# uc_sram.net
KiCad netlist of a schematic drawn in Altium Designer
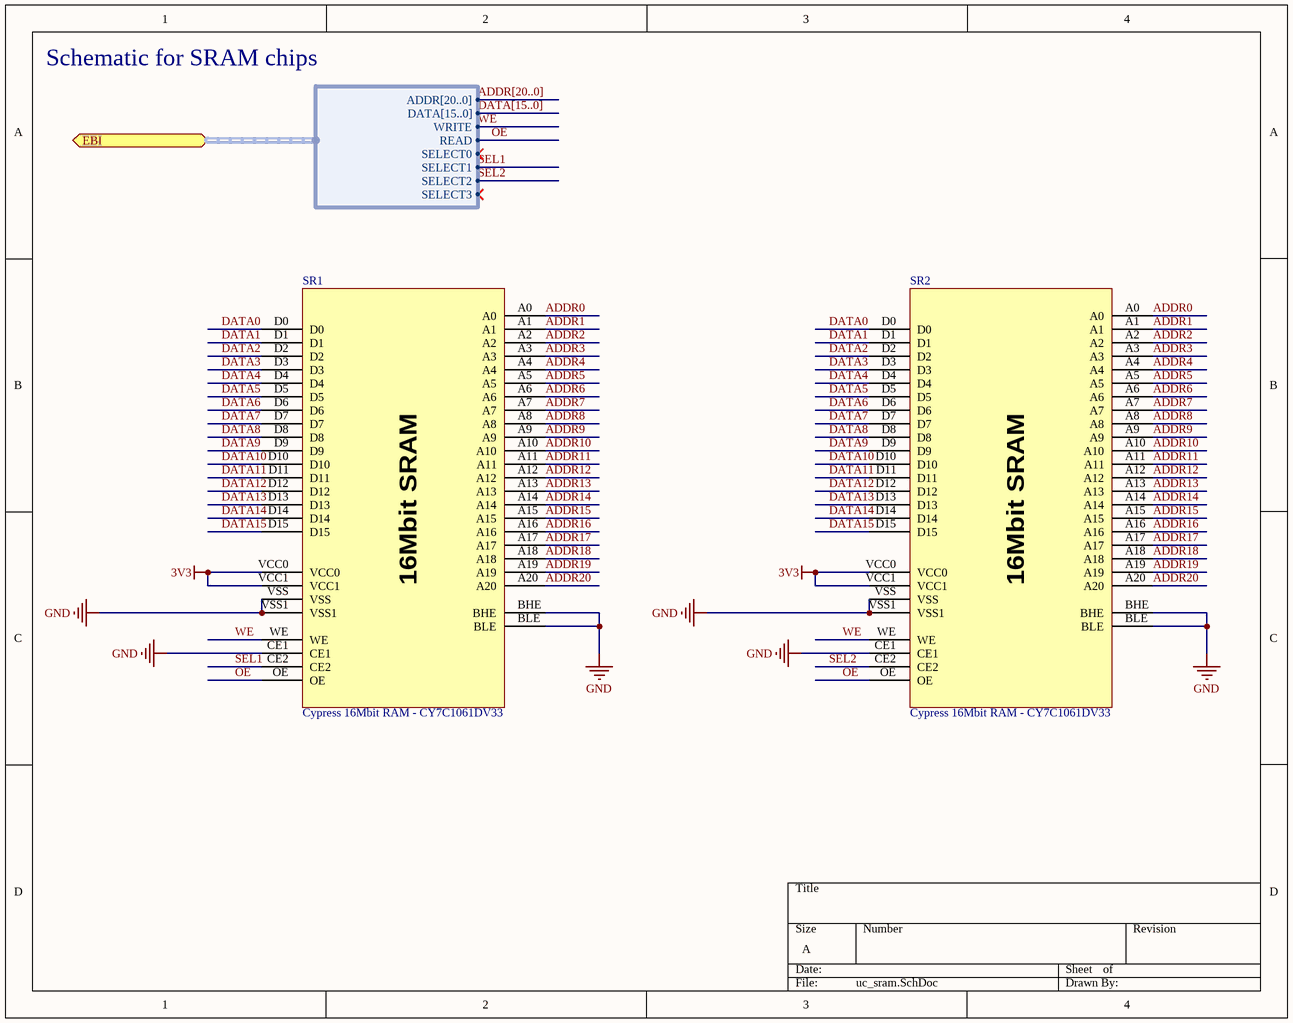
[diagram p0: uc_sram.SchDoc]

(export (version "E")
  (design (tool "Eeschema 10.0.6"))
  (components
    (comp (ref "SR1")
      (value "Cypress 16Mbit RAM - CY7C1061DV33")
      (footprint "BGA48C75P8X6_950X800X100")
      (libsource (lib "ORLY_Lib") (part "Cypress 16Mbit RAM - CY7C1061DV33"))
    )
    (comp (ref "SR2")
      (value "Cypress 16Mbit RAM - CY7C1061DV33")
      (footprint "BGA48C75P8X6_950X800X100")
      (libsource (lib "ORLY_Lib") (part "Cypress 16Mbit RAM - CY7C1061DV33"))
    )
  )
  (nets
    (net (code "2") (name "/ADDR0") (class "Default")
      (node (ref "SR1") (pin "A0") (pinfunction "A0_A0") (pintype "passive"))
      (node (ref "SR2") (pin "A0") (pinfunction "A0_A0") (pintype "passive"))
    )
    (net (code "3") (name "/ADDR1") (class "Default")
      (node (ref "SR1") (pin "A1") (pinfunction "A1_A1") (pintype "passive"))
      (node (ref "SR2") (pin "A1") (pinfunction "A1_A1") (pintype "passive"))
    )
    (net (code "4") (name "/ADDR2") (class "Default")
      (node (ref "SR1") (pin "A2") (pinfunction "A2_A2") (pintype "passive"))
      (node (ref "SR2") (pin "A2") (pinfunction "A2_A2") (pintype "passive"))
    )
    (net (code "5") (name "/ADDR3") (class "Default")
      (node (ref "SR1") (pin "A3") (pinfunction "A3_A3") (pintype "passive"))
      (node (ref "SR2") (pin "A3") (pinfunction "A3_A3") (pintype "passive"))
    )
    (net (code "6") (name "/ADDR4") (class "Default")
      (node (ref "SR1") (pin "A4") (pinfunction "A4_A4") (pintype "passive"))
      (node (ref "SR2") (pin "A4") (pinfunction "A4_A4") (pintype "passive"))
    )
    (net (code "7") (name "/ADDR5") (class "Default")
      (node (ref "SR1") (pin "A5") (pinfunction "A5_A5") (pintype "passive"))
      (node (ref "SR2") (pin "A5") (pinfunction "A5_A5") (pintype "passive"))
    )
    (net (code "8") (name "/ADDR6") (class "Default")
      (node (ref "SR1") (pin "A6") (pinfunction "A6_A6") (pintype "passive"))
      (node (ref "SR2") (pin "A6") (pinfunction "A6_A6") (pintype "passive"))
    )
    (net (code "9") (name "/ADDR7") (class "Default")
      (node (ref "SR1") (pin "A7") (pinfunction "A7_A7") (pintype "passive"))
      (node (ref "SR2") (pin "A7") (pinfunction "A7_A7") (pintype "passive"))
    )
    (net (code "10") (name "/ADDR8") (class "Default")
      (node (ref "SR1") (pin "A8") (pinfunction "A8_A8") (pintype "passive"))
      (node (ref "SR2") (pin "A8") (pinfunction "A8_A8") (pintype "passive"))
    )
    (net (code "11") (name "/ADDR9") (class "Default")
      (node (ref "SR1") (pin "A9") (pinfunction "A9_A9") (pintype "passive"))
      (node (ref "SR2") (pin "A9") (pinfunction "A9_A9") (pintype "passive"))
    )
    (net (code "12") (name "/ADDR10") (class "Default")
      (node (ref "SR1") (pin "A10") (pinfunction "A10_A10") (pintype "passive"))
      (node (ref "SR2") (pin "A10") (pinfunction "A10_A10") (pintype "passive"))
    )
    (net (code "13") (name "/ADDR11") (class "Default")
      (node (ref "SR1") (pin "A11") (pinfunction "A11_A11") (pintype "passive"))
      (node (ref "SR2") (pin "A11") (pinfunction "A11_A11") (pintype "passive"))
    )
    (net (code "14") (name "/ADDR12") (class "Default")
      (node (ref "SR1") (pin "A12") (pinfunction "A12_A12") (pintype "passive"))
      (node (ref "SR2") (pin "A12") (pinfunction "A12_A12") (pintype "passive"))
    )
    (net (code "15") (name "/ADDR13") (class "Default")
      (node (ref "SR1") (pin "A13") (pinfunction "A13_A13") (pintype "passive"))
      (node (ref "SR2") (pin "A13") (pinfunction "A13_A13") (pintype "passive"))
    )
    (net (code "16") (name "/ADDR14") (class "Default")
      (node (ref "SR1") (pin "A14") (pinfunction "A14_A14") (pintype "passive"))
      (node (ref "SR2") (pin "A14") (pinfunction "A14_A14") (pintype "passive"))
    )
    (net (code "17") (name "/ADDR15") (class "Default")
      (node (ref "SR1") (pin "A15") (pinfunction "A15_A15") (pintype "passive"))
      (node (ref "SR2") (pin "A15") (pinfunction "A15_A15") (pintype "passive"))
    )
    (net (code "18") (name "/ADDR16") (class "Default")
      (node (ref "SR1") (pin "A16") (pinfunction "A16_A16") (pintype "passive"))
      (node (ref "SR2") (pin "A16") (pinfunction "A16_A16") (pintype "passive"))
    )
    (net (code "19") (name "/ADDR17") (class "Default")
      (node (ref "SR1") (pin "A17") (pinfunction "A17_A17") (pintype "passive"))
      (node (ref "SR2") (pin "A17") (pinfunction "A17_A17") (pintype "passive"))
    )
    (net (code "20") (name "/ADDR18") (class "Default")
      (node (ref "SR1") (pin "A18") (pinfunction "A18_A18") (pintype "passive"))
      (node (ref "SR2") (pin "A18") (pinfunction "A18_A18") (pintype "passive"))
    )
    (net (code "21") (name "/ADDR19") (class "Default")
      (node (ref "SR1") (pin "A19") (pinfunction "A19_A19") (pintype "passive"))
      (node (ref "SR2") (pin "A19") (pinfunction "A19_A19") (pintype "passive"))
    )
    (net (code "22") (name "/ADDR20") (class "Default")
      (node (ref "SR1") (pin "A20") (pinfunction "A20_A20") (pintype "passive"))
      (node (ref "SR2") (pin "A20") (pinfunction "A20_A20") (pintype "passive"))
    )
    (net (code "24") (name "/DATA0") (class "Default")
      (node (ref "SR1") (pin "D0") (pinfunction "D0_D0") (pintype "passive"))
      (node (ref "SR2") (pin "D0") (pinfunction "D0_D0") (pintype "passive"))
    )
    (net (code "25") (name "/DATA1") (class "Default")
      (node (ref "SR1") (pin "D1") (pinfunction "D1_D1") (pintype "passive"))
      (node (ref "SR2") (pin "D1") (pinfunction "D1_D1") (pintype "passive"))
    )
    (net (code "26") (name "/DATA2") (class "Default")
      (node (ref "SR1") (pin "D2") (pinfunction "D2_D2") (pintype "passive"))
      (node (ref "SR2") (pin "D2") (pinfunction "D2_D2") (pintype "passive"))
    )
    (net (code "27") (name "/DATA3") (class "Default")
      (node (ref "SR1") (pin "D3") (pinfunction "D3_D3") (pintype "passive"))
      (node (ref "SR2") (pin "D3") (pinfunction "D3_D3") (pintype "passive"))
    )
    (net (code "28") (name "/DATA4") (class "Default")
      (node (ref "SR1") (pin "D4") (pinfunction "D4_D4") (pintype "passive"))
      (node (ref "SR2") (pin "D4") (pinfunction "D4_D4") (pintype "passive"))
    )
    (net (code "29") (name "/DATA5") (class "Default")
      (node (ref "SR1") (pin "D5") (pinfunction "D5_D5") (pintype "passive"))
      (node (ref "SR2") (pin "D5") (pinfunction "D5_D5") (pintype "passive"))
    )
    (net (code "30") (name "/DATA6") (class "Default")
      (node (ref "SR1") (pin "D6") (pinfunction "D6_D6") (pintype "passive"))
      (node (ref "SR2") (pin "D6") (pinfunction "D6_D6") (pintype "passive"))
    )
    (net (code "31") (name "/DATA7") (class "Default")
      (node (ref "SR1") (pin "D7") (pinfunction "D7_D7") (pintype "passive"))
      (node (ref "SR2") (pin "D7") (pinfunction "D7_D7") (pintype "passive"))
    )
    (net (code "32") (name "/DATA8") (class "Default")
      (node (ref "SR1") (pin "D8") (pinfunction "D8_D8") (pintype "passive"))
      (node (ref "SR2") (pin "D8") (pinfunction "D8_D8") (pintype "passive"))
    )
    (net (code "33") (name "/DATA9") (class "Default")
      (node (ref "SR1") (pin "D9") (pinfunction "D9_D9") (pintype "passive"))
      (node (ref "SR2") (pin "D9") (pinfunction "D9_D9") (pintype "passive"))
    )
    (net (code "34") (name "/DATA10") (class "Default")
      (node (ref "SR1") (pin "D10") (pinfunction "D10_D10") (pintype "passive"))
      (node (ref "SR2") (pin "D10") (pinfunction "D10_D10") (pintype "passive"))
    )
    (net (code "35") (name "/DATA11") (class "Default")
      (node (ref "SR1") (pin "D11") (pinfunction "D11_D11") (pintype "passive"))
      (node (ref "SR2") (pin "D11") (pinfunction "D11_D11") (pintype "passive"))
    )
    (net (code "36") (name "/DATA12") (class "Default")
      (node (ref "SR1") (pin "D12") (pinfunction "D12_D12") (pintype "passive"))
      (node (ref "SR2") (pin "D12") (pinfunction "D12_D12") (pintype "passive"))
    )
    (net (code "37") (name "/DATA13") (class "Default")
      (node (ref "SR1") (pin "D13") (pinfunction "D13_D13") (pintype "passive"))
      (node (ref "SR2") (pin "D13") (pinfunction "D13_D13") (pintype "passive"))
    )
    (net (code "38") (name "/DATA14") (class "Default")
      (node (ref "SR1") (pin "D14") (pinfunction "D14_D14") (pintype "passive"))
      (node (ref "SR2") (pin "D14") (pinfunction "D14_D14") (pintype "passive"))
    )
    (net (code "39") (name "/DATA15") (class "Default")
      (node (ref "SR1") (pin "D15") (pinfunction "D15_D15") (pintype "passive"))
      (node (ref "SR2") (pin "D15") (pinfunction "D15_D15") (pintype "passive"))
    )
    (net (code "41") (name "/OE") (class "Default")
      (node (ref "SR1") (pin "OE") (pinfunction "OE_OE") (pintype "passive"))
      (node (ref "SR2") (pin "OE") (pinfunction "OE_OE") (pintype "passive"))
    )
    (net (code "42") (name "/SEL1") (class "Default")
      (node (ref "SR1") (pin "CE2") (pinfunction "CE2_CE2") (pintype "passive"))
    )
    (net (code "43") (name "/SEL2") (class "Default")
      (node (ref "SR2") (pin "CE2") (pinfunction "CE2_CE2") (pintype "passive"))
    )
    (net (code "44") (name "/WE") (class "Default")
      (node (ref "SR1") (pin "WE") (pinfunction "WE_WE") (pintype "passive"))
      (node (ref "SR2") (pin "WE") (pinfunction "WE_WE") (pintype "passive"))
    )
    (net (code "45") (name "3V3") (class "Default")
      (node (ref "SR1") (pin "VCC0") (pinfunction "VCC0_VCC0") (pintype "passive"))
      (node (ref "SR1") (pin "VCC1") (pinfunction "VCC1_VCC1") (pintype "passive"))
      (node (ref "SR2") (pin "VCC0") (pinfunction "VCC0_VCC0") (pintype "passive"))
      (node (ref "SR2") (pin "VCC1") (pinfunction "VCC1_VCC1") (pintype "passive"))
    )
    (net (code "46") (name "GND") (class "Default")
      (node (ref "SR1") (pin "BHE") (pinfunction "BHE_BHE") (pintype "passive"))
      (node (ref "SR1") (pin "BLE") (pinfunction "BLE_BLE") (pintype "passive"))
      (node (ref "SR1") (pin "CE1") (pinfunction "CE1_CE1") (pintype "passive"))
      (node (ref "SR1") (pin "VSS") (pinfunction "VSS_VSS") (pintype "passive"))
      (node (ref "SR1") (pin "VSS1") (pinfunction "VSS1_VSS1") (pintype "passive"))
      (node (ref "SR2") (pin "BHE") (pinfunction "BHE_BHE") (pintype "passive"))
      (node (ref "SR2") (pin "BLE") (pinfunction "BLE_BLE") (pintype "passive"))
      (node (ref "SR2") (pin "CE1") (pinfunction "CE1_CE1") (pintype "passive"))
      (node (ref "SR2") (pin "VSS") (pinfunction "VSS_VSS") (pintype "passive"))
      (node (ref "SR2") (pin "VSS1") (pinfunction "VSS1_VSS1") (pintype "passive"))
    )
  )
)
